# Attuino-v2a.net
KiCad netlist of a schematic drawn in EAGLE
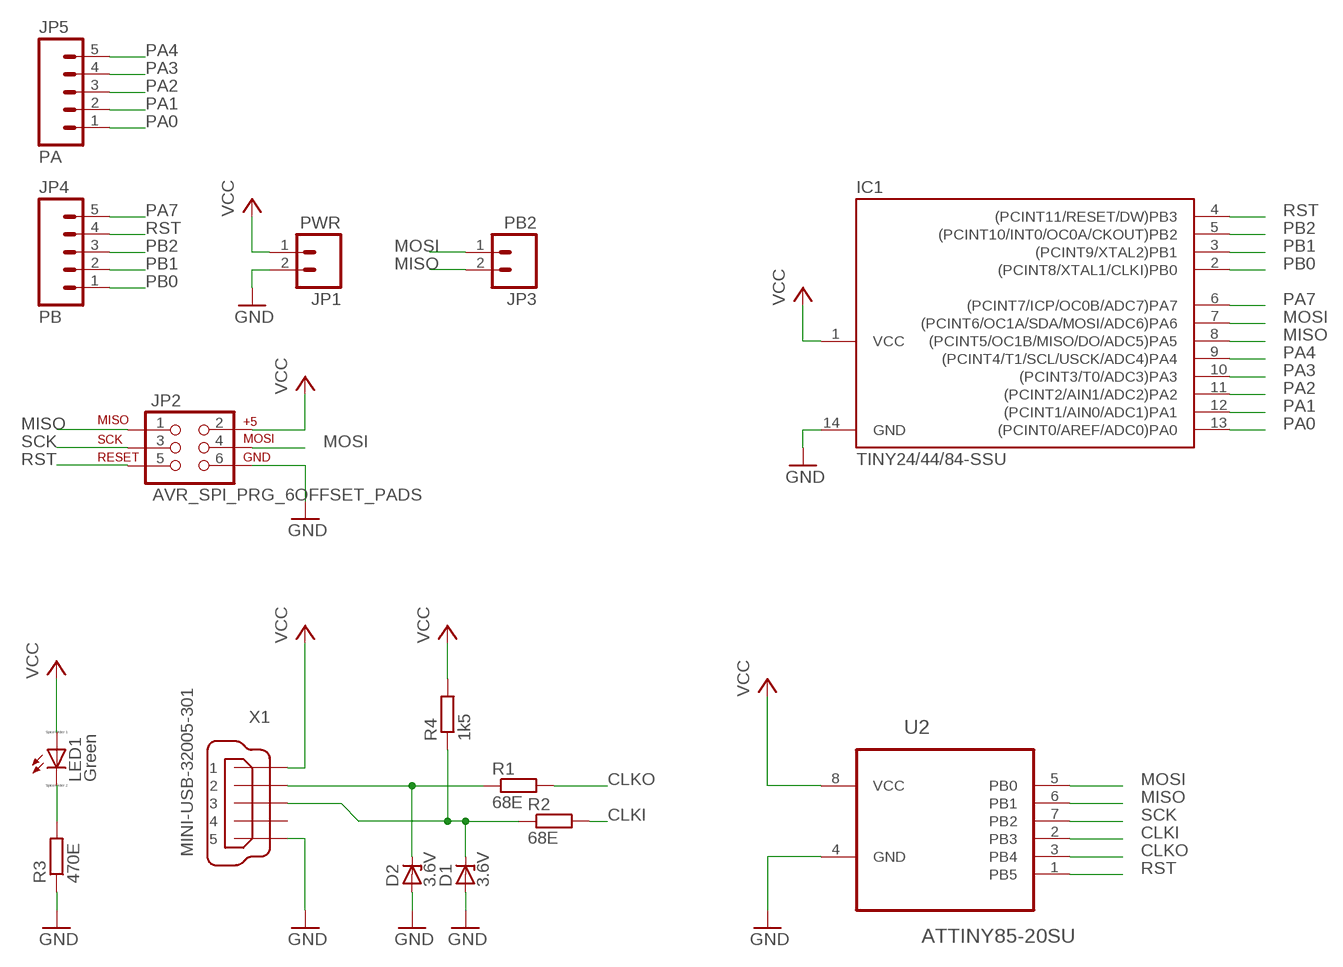
[diagram p0: schematic, sheet 1]

(export (version "E")
  (design (tool "Eeschema 10.0.6"))
  (components
    (comp (ref "D1")
      (value "3.6V")
      (footprint "eagle-import:SOD80C")
      (libsource (lib "eagle-import") (part "ZENER-DIODESOD80C"))
    )
    (comp (ref "D2")
      (value "3.6V")
      (footprint "eagle-import:SOD80C")
      (libsource (lib "eagle-import") (part "ZENER-DIODESOD80C"))
    )
    (comp (ref "IC1")
      (value "TINY24/44/84-SSU")
      (footprint "eagle-import:SOIC14")
      (libsource (lib "eagle-import") (part "TINY24/44/84-SSU"))
    )
    (comp (ref "JP1")
      (value "PWR")
      (footprint "eagle-import:1X02_NO_SILK")
      (libsource (lib "eagle-import") (part "M021X02_NO_SILK"))
    )
    (comp (ref "JP2")
      (value "AVR_SPI_PRG_6OFFSET_PADS")
      (footprint "eagle-import:2X3_OFFSET")
      (libsource (lib "eagle-import") (part "AVR_SPI_PRG_6OFFSET_PADS"))
    )
    (comp (ref "JP3")
      (value "PB2")
      (footprint "eagle-import:1X02_NO_SILK")
      (libsource (lib "eagle-import") (part "M021X02_NO_SILK"))
    )
    (comp (ref "JP4")
      (value "PB")
      (footprint "eagle-import:1X05_NO_SILK")
      (libsource (lib "eagle-import") (part "M05NO_SILK"))
    )
    (comp (ref "JP5")
      (value "PA")
      (footprint "eagle-import:1X05_NO_SILK")
      (libsource (lib "eagle-import") (part "M05NO_SILK"))
    )
    (comp (ref "LED1")
      (value "Green")
      (footprint "eagle-import:LED_1206")
      (libsource (lib "eagle-import") (part "LED_E"))
    )
    (comp (ref "R1")
      (value "68E")
      (footprint "eagle-import:R0805")
      (libsource (lib "eagle-import") (part "R-EU_R0805"))
    )
    (comp (ref "R2")
      (value "68E")
      (footprint "eagle-import:R0805")
      (libsource (lib "eagle-import") (part "R-EU_R0805"))
    )
    (comp (ref "R3")
      (value "470E")
      (footprint "eagle-import:R0805")
      (libsource (lib "eagle-import") (part "R-EU_R0805"))
    )
    (comp (ref "R4")
      (value "1k5")
      (footprint "eagle-import:R0805")
      (libsource (lib "eagle-import") (part "R-EU_R0805"))
    )
    (comp (ref "U2")
      (value "ATTINY85-20SU")
      (footprint "eagle-import:SOIC127P798X216-8N")
      (libsource (lib "eagle-import") (part "ATTINY85-20SU"))
    )
    (comp (ref "X1")
      (value "MINI-USB-32005-301")
      (footprint "eagle-import:32005-301")
      (libsource (lib "eagle-import") (part "MINI-USB-32005-301"))
    )
  )
  (nets
    (net (code "1") (name "/CLKI") (class "Default")
      (node (ref "R2") (pin "2") (pinfunction "2_2") (pintype "passive"))
      (node (ref "U2") (pin "2") (pinfunction "PB3_2") (pintype "bidirectional"))
    )
    (net (code "2") (name "/CLKO") (class "Default")
      (node (ref "R1") (pin "2") (pinfunction "2_2") (pintype "passive"))
      (node (ref "U2") (pin "3") (pinfunction "PB4_3") (pintype "bidirectional"))
    )
    (net (code "3") (name "/MISO") (class "Default")
      (node (ref "IC1") (pin "8") (pinfunction "(PCINT5/OC1B/MISO/DO/ADC5)PA5_8") (pintype "bidirectional"))
      (node (ref "JP2") (pin "1") (pinfunction "1_1") (pintype "passive"))
      (node (ref "JP3") (pin "2") (pinfunction "2_2") (pintype "passive"))
      (node (ref "U2") (pin "6") (pinfunction "PB1_6") (pintype "bidirectional"))
    )
    (net (code "4") (name "/MOSI") (class "Default")
      (node (ref "IC1") (pin "7") (pinfunction "(PCINT6/OC1A/SDA/MOSI/ADC6)PA6_7") (pintype "bidirectional"))
      (node (ref "JP2") (pin "4") (pinfunction "4_4") (pintype "passive"))
      (node (ref "JP3") (pin "1") (pinfunction "1_1") (pintype "passive"))
      (node (ref "U2") (pin "5") (pinfunction "PB0_5") (pintype "bidirectional"))
    )
    (net (code "5") (name "/PA0") (class "Default")
      (node (ref "IC1") (pin "13") (pinfunction "(PCINT0/AREF/ADC0)PA0_13") (pintype "bidirectional"))
      (node (ref "JP5") (pin "1") (pinfunction "1_1") (pintype "passive"))
    )
    (net (code "6") (name "/PA1") (class "Default")
      (node (ref "IC1") (pin "12") (pinfunction "(PCINT1/AIN0/ADC1)PA1_12") (pintype "bidirectional"))
      (node (ref "JP5") (pin "2") (pinfunction "2_2") (pintype "passive"))
    )
    (net (code "7") (name "/PA2") (class "Default")
      (node (ref "IC1") (pin "11") (pinfunction "(PCINT2/AIN1/ADC2)PA2_11") (pintype "bidirectional"))
      (node (ref "JP5") (pin "3") (pinfunction "3_3") (pintype "passive"))
    )
    (net (code "8") (name "/PA3") (class "Default")
      (node (ref "IC1") (pin "10") (pinfunction "(PCINT3/T0/ADC3)PA3_10") (pintype "bidirectional"))
      (node (ref "JP5") (pin "4") (pinfunction "4_4") (pintype "passive"))
    )
    (net (code "9") (name "/PA4") (class "Default")
      (node (ref "IC1") (pin "9") (pinfunction "(PCINT4/T1/SCL/USCK/ADC4)PA4_9") (pintype "bidirectional"))
      (node (ref "JP5") (pin "5") (pinfunction "5_5") (pintype "passive"))
    )
    (net (code "10") (name "/PA7") (class "Default")
      (node (ref "IC1") (pin "6") (pinfunction "(PCINT7/ICP/OC0B/ADC7)PA7_6") (pintype "bidirectional"))
      (node (ref "JP4") (pin "5") (pinfunction "5_5") (pintype "passive"))
    )
    (net (code "11") (name "/PB0") (class "Default")
      (node (ref "IC1") (pin "2") (pinfunction "(PCINT8/XTAL1/CLKI)PB0_2") (pintype "bidirectional"))
      (node (ref "JP4") (pin "1") (pinfunction "1_1") (pintype "passive"))
    )
    (net (code "12") (name "/PB1") (class "Default")
      (node (ref "IC1") (pin "3") (pinfunction "(PCINT9/XTAL2)PB1_3") (pintype "bidirectional"))
      (node (ref "JP4") (pin "2") (pinfunction "2_2") (pintype "passive"))
    )
    (net (code "13") (name "/PB2") (class "Default")
      (node (ref "IC1") (pin "5") (pinfunction "(PCINT10/INT0/OC0A/CKOUT)PB2_5") (pintype "bidirectional"))
      (node (ref "JP4") (pin "3") (pinfunction "3_3") (pintype "passive"))
    )
    (net (code "14") (name "/RST") (class "Default")
      (node (ref "IC1") (pin "4") (pinfunction "(PCINT11/RESET/DW)PB3_4") (pintype "bidirectional"))
      (node (ref "JP2") (pin "5") (pinfunction "5_5") (pintype "passive"))
      (node (ref "JP4") (pin "4") (pinfunction "4_4") (pintype "passive"))
      (node (ref "U2") (pin "1") (pinfunction "PB5_1") (pintype "bidirectional"))
    )
    (net (code "15") (name "/SCK") (class "Default")
      (node (ref "JP2") (pin "3") (pinfunction "3_3") (pintype "passive"))
      (node (ref "U2") (pin "7") (pinfunction "PB2_7") (pintype "bidirectional"))
    )
    (net (code "16") (name "GND") (class "Default")
      (node (ref "D1") (pin "A") (pinfunction "A_A") (pintype "passive"))
      (node (ref "D2") (pin "A") (pinfunction "A_A") (pintype "passive"))
      (node (ref "IC1") (pin "14") (pinfunction "GND_14") (pintype "power_in"))
      (node (ref "JP1") (pin "2") (pinfunction "2_2") (pintype "passive"))
      (node (ref "JP2") (pin "6") (pinfunction "6_6") (pintype "passive"))
      (node (ref "R3") (pin "1") (pinfunction "1_1") (pintype "passive"))
      (node (ref "U2") (pin "4") (pinfunction "GND_4") (pintype "passive"))
      (node (ref "X1") (pin "5") (pinfunction "5_5") (pintype "passive"))
    )
    (net (code "17") (name "Net-(D1-PadC)") (class "Default")
      (node (ref "D1") (pin "C") (pinfunction "C_C") (pintype "passive"))
      (node (ref "R2") (pin "1") (pinfunction "1_1") (pintype "passive"))
      (node (ref "R4") (pin "1") (pinfunction "1_1") (pintype "passive"))
      (node (ref "X1") (pin "3") (pinfunction "3_3") (pintype "passive"))
    )
    (net (code "18") (name "Net-(D2-PadC)") (class "Default")
      (node (ref "D2") (pin "C") (pinfunction "C_C") (pintype "passive"))
      (node (ref "R1") (pin "1") (pinfunction "1_1") (pintype "passive"))
      (node (ref "X1") (pin "2") (pinfunction "2_2") (pintype "passive"))
    )
    (net (code "19") (name "Net-(LED1-PadC)") (class "Default")
      (node (ref "LED1") (pin "C") (pinfunction "C_C") (pintype "passive"))
      (node (ref "R3") (pin "2") (pinfunction "2_2") (pintype "passive"))
    )
    (net (code "20") (name "VCC") (class "Default")
      (node (ref "IC1") (pin "1") (pinfunction "VCC_1") (pintype "power_in"))
      (node (ref "JP1") (pin "1") (pinfunction "1_1") (pintype "passive"))
      (node (ref "JP2") (pin "2") (pinfunction "2_2") (pintype "passive"))
      (node (ref "LED1") (pin "A") (pinfunction "A_A") (pintype "passive"))
      (node (ref "R4") (pin "2") (pinfunction "2_2") (pintype "passive"))
      (node (ref "U2") (pin "8") (pinfunction "VCC_8") (pintype "power_in"))
      (node (ref "X1") (pin "1") (pinfunction "1_1") (pintype "passive"))
    )
    (net (code "21") (name "unconnected-(X1-Pad4)") (class "Default")
      (node (ref "X1") (pin "4") (pinfunction "4_4") (pintype "passive"))
    )
  )
)
